# gondola.net
KiCad netlist of a schematic drawn in EAGLE
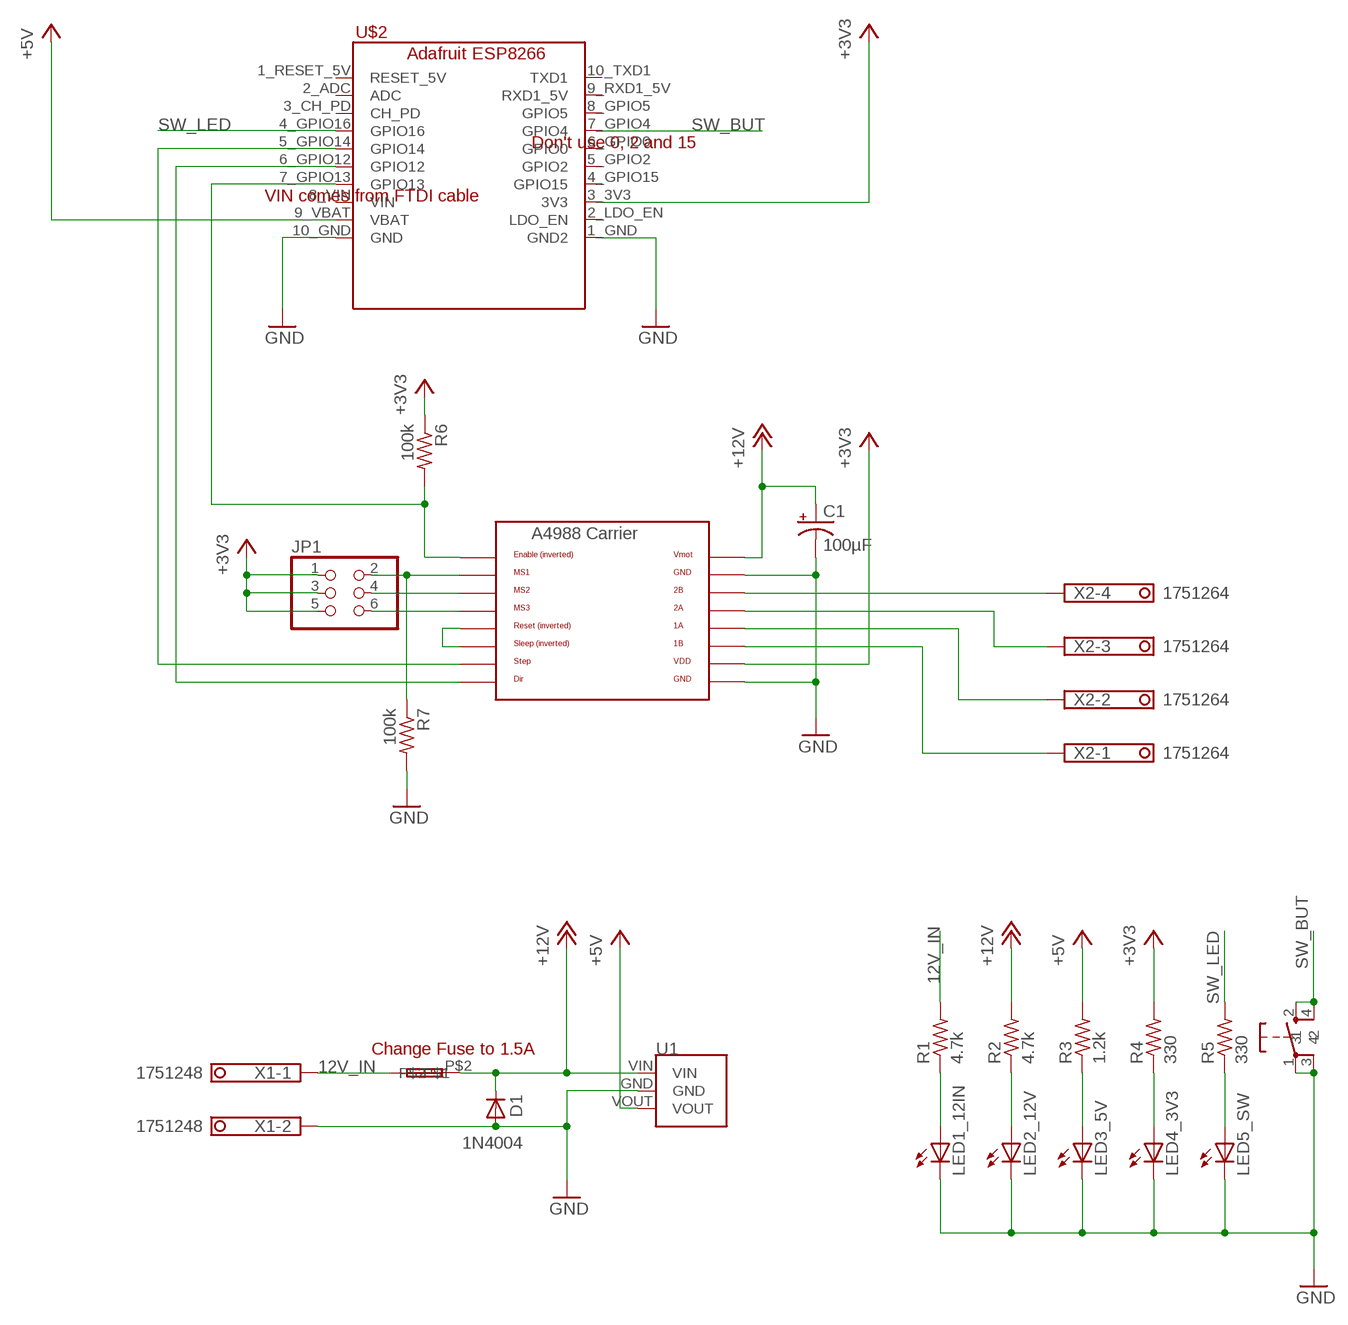
[diagram p0: schematic, sheet 1]

(export (version "E")
  (design (tool "Eeschema 10.0.6"))
  (components
    (comp (ref "C1")
      (value "100µF")
      (footprint "eagle-import:153CLV-0605")
      (libsource (lib "eagle-import") (part "CPOL-US153CLV-0605"))
    )
    (comp (ref "D1")
      (value "1N4004")
      (footprint "eagle-import:DO41-10")
      (libsource (lib "eagle-import") (part "1N4004"))
    )
    (comp (ref "F1")
      (value "MFR500")
      (footprint "eagle-import:MFR500")
      (libsource (lib "eagle-import") (part "MFR500"))
    )
    (comp (ref "JP1")
      (value "PINHD-2X3")
      (footprint "eagle-import:2X03")
      (libsource (lib "eagle-import") (part "PINHD-2X3"))
    )
    (comp (ref "LED1_12IN")
      (value "LEDCHIP-LED0805")
      (footprint "eagle-import:CHIP-LED0805")
      (libsource (lib "eagle-import") (part "LEDCHIP-LED0805"))
    )
    (comp (ref "LED2_12V")
      (value "LEDCHIP-LED0805")
      (footprint "eagle-import:CHIP-LED0805")
      (libsource (lib "eagle-import") (part "LEDCHIP-LED0805"))
    )
    (comp (ref "LED3_5V")
      (value "LEDCHIP-LED0805")
      (footprint "eagle-import:CHIP-LED0805")
      (libsource (lib "eagle-import") (part "LEDCHIP-LED0805"))
    )
    (comp (ref "LED4_3V3")
      (value "LEDCHIP-LED0805")
      (footprint "eagle-import:CHIP-LED0805")
      (libsource (lib "eagle-import") (part "LEDCHIP-LED0805"))
    )
    (comp (ref "LED5_SW")
      (value "LEDCHIP-LED0805")
      (footprint "eagle-import:CHIP-LED0805")
      (libsource (lib "eagle-import") (part "LEDCHIP-LED0805"))
    )
    (comp (ref "R1")
      (value "4.7k")
      (footprint "eagle-import:R0805")
      (libsource (lib "eagle-import") (part "R-US_R0805"))
    )
    (comp (ref "R2")
      (value "4.7k")
      (footprint "eagle-import:R0805")
      (libsource (lib "eagle-import") (part "R-US_R0805"))
    )
    (comp (ref "R3")
      (value "1.2k")
      (footprint "eagle-import:R0805")
      (libsource (lib "eagle-import") (part "R-US_R0805"))
    )
    (comp (ref "R4")
      (value "330")
      (footprint "eagle-import:R0805")
      (libsource (lib "eagle-import") (part "R-US_R0805"))
    )
    (comp (ref "R5")
      (value "330")
      (footprint "eagle-import:R0805")
      (libsource (lib "eagle-import") (part "R-US_R0805"))
    )
    (comp (ref "R6")
      (value "100k")
      (footprint "eagle-import:R0805")
      (libsource (lib "eagle-import") (part "R-US_R0805"))
    )
    (comp (ref "R7")
      (value "100k")
      (footprint "eagle-import:R0805")
      (libsource (lib "eagle-import") (part "R-US_R0805"))
    )
    (comp (ref "U$1")
      (value "A4988BREAKOUT")
      (footprint "eagle-import:A4988BREAKOUT")
      (libsource (lib "eagle-import") (part "A4988BREAKOUT"))
    )
    (comp (ref "U$2")
      (value "ADAFRUIT_ESP8266")
      (footprint "eagle-import:ADAFRUIT_ESP8266")
      (libsource (lib "eagle-import") (part "ADAFRUIT_ESP8266"))
    )
    (comp (ref "U$4")
      (value "FSMCTTR")
      (footprint "eagle-import:FSMCTTR")
      (libsource (lib "eagle-import") (part "FSMCTTR"))
    )
    (comp (ref "U1")
      (value "ROHM_BP5293-XX")
      (footprint "eagle-import:ROHM_BP5293-XX")
      (libsource (lib "eagle-import") (part "ROHM_BP5293-XX"))
    )
    (comp (ref "X1")
      (value "1751248")
      (footprint "eagle-import:1751248")
      (libsource (lib "eagle-import") (part "1751248"))
    )
    (comp (ref "X2")
      (value "1751264")
      (footprint "eagle-import:1751264")
      (libsource (lib "eagle-import") (part "1751264"))
    )
  )
  (nets
    (net (code "1") (name "+3V3") (class "Default")
      (node (ref "JP1") (pin "1") (pinfunction "1_1") (pintype "passive"))
      (node (ref "JP1") (pin "3") (pinfunction "3_3") (pintype "passive"))
      (node (ref "JP1") (pin "5") (pinfunction "5_5") (pintype "passive"))
      (node (ref "R4") (pin "2") (pinfunction "2_2") (pintype "passive"))
      (node (ref "R6") (pin "1") (pinfunction "1_1") (pintype "passive"))
      (node (ref "U$1") (pin "VDD") (pinfunction "VDD_VDD") (pintype "power_in"))
      (node (ref "U$2") (pin "3_3V3") (pinfunction "3V3_3_3V3") (pintype "bidirectional"))
    )
    (net (code "2") (name "+5V") (class "Default")
      (node (ref "R3") (pin "2") (pinfunction "2_2") (pintype "passive"))
      (node (ref "U$2") (pin "9_VBAT") (pinfunction "VBAT_9_VBAT") (pintype "bidirectional"))
      (node (ref "U1") (pin "VOUT") (pinfunction "VOUT_VOUT") (pintype "bidirectional"))
    )
    (net (code "3") (name "+12V") (class "Default")
      (node (ref "C1") (pin "+") (pinfunction "+_+") (pintype "passive"))
      (node (ref "D1") (pin "C") (pinfunction "C_C") (pintype "passive"))
      (node (ref "F1") (pin "P$2") (pinfunction "P$2_P$2") (pintype "bidirectional"))
      (node (ref "R2") (pin "2") (pinfunction "2_2") (pintype "passive"))
      (node (ref "U$1") (pin "VMOT") (pinfunction "VMOT_VMOT") (pintype "power_in"))
      (node (ref "U1") (pin "VIN") (pinfunction "VIN_VIN") (pintype "bidirectional"))
    )
    (net (code "4") (name "/12V_IN") (class "Default")
      (node (ref "F1") (pin "P$1") (pinfunction "P$1_P$1") (pintype "bidirectional"))
      (node (ref "R1") (pin "2") (pinfunction "2_2") (pintype "passive"))
      (node (ref "X1") (pin "1") (pinfunction "K_1") (pintype "passive"))
    )
    (net (code "5") (name "/SW_BUT") (class "Default")
      (node (ref "U$2") (pin "7_GPIO4") (pinfunction "GPIO4_7_GPIO4") (pintype "bidirectional"))
      (node (ref "U$4") (pin "2") (pinfunction "3_2") (pintype "bidirectional"))
      (node (ref "U$4") (pin "4") (pinfunction "4_4") (pintype "bidirectional"))
    )
    (net (code "6") (name "/SW_LED") (class "Default")
      (node (ref "R5") (pin "2") (pinfunction "2_2") (pintype "passive"))
      (node (ref "U$2") (pin "4_GPIO16") (pinfunction "GPIO16_4_GPIO16") (pintype "bidirectional"))
    )
    (net (code "7") (name "GND") (class "Default")
      (node (ref "C1") (pin "-") (pinfunction "-_-") (pintype "passive"))
      (node (ref "D1") (pin "A") (pinfunction "A_A") (pintype "passive"))
      (node (ref "LED1_12IN") (pin "C") (pinfunction "C_C") (pintype "passive"))
      (node (ref "LED2_12V") (pin "C") (pinfunction "C_C") (pintype "passive"))
      (node (ref "LED3_5V") (pin "C") (pinfunction "C_C") (pintype "passive"))
      (node (ref "LED4_3V3") (pin "C") (pinfunction "C_C") (pintype "passive"))
      (node (ref "LED5_SW") (pin "C") (pinfunction "C_C") (pintype "passive"))
      (node (ref "R7") (pin "2") (pinfunction "2_2") (pintype "passive"))
      (node (ref "U$1") (pin "GND") (pinfunction "GND_GND") (pintype "power_in"))
      (node (ref "U$1") (pin "GND@0") (pinfunction "GND_GND@0") (pintype "power_in"))
      (node (ref "U$2") (pin "10_GND") (pinfunction "GND_10_GND") (pintype "bidirectional"))
      (node (ref "U$2") (pin "1_GND") (pinfunction "GND2_1_GND") (pintype "bidirectional"))
      (node (ref "U$4") (pin "1") (pinfunction "1_1") (pintype "bidirectional"))
      (node (ref "U$4") (pin "3") (pinfunction "2_3") (pintype "bidirectional"))
      (node (ref "U1") (pin "GND") (pinfunction "GND_GND") (pintype "bidirectional"))
      (node (ref "X1") (pin "2") (pinfunction "K_2") (pintype "passive"))
    )
    (net (code "8") (name "Net-(JP1-Pad2)") (class "Default")
      (node (ref "JP1") (pin "2") (pinfunction "2_2") (pintype "passive"))
      (node (ref "R7") (pin "1") (pinfunction "1_1") (pintype "passive"))
      (node (ref "U$1") (pin "MS1") (pinfunction "MS1_MS1") (pintype "input"))
    )
    (net (code "9") (name "Net-(JP1-Pad4)") (class "Default")
      (node (ref "JP1") (pin "4") (pinfunction "4_4") (pintype "passive"))
      (node (ref "U$1") (pin "MS2") (pinfunction "MS2_MS2") (pintype "input"))
    )
    (net (code "10") (name "Net-(JP1-Pad6)") (class "Default")
      (node (ref "JP1") (pin "6") (pinfunction "6_6") (pintype "passive"))
      (node (ref "U$1") (pin "MS3") (pinfunction "MS3_MS3") (pintype "input"))
    )
    (net (code "11") (name "Net-(LED1_12IN-PadA)") (class "Default")
      (node (ref "LED1_12IN") (pin "A") (pinfunction "A_A") (pintype "passive"))
      (node (ref "R1") (pin "1") (pinfunction "1_1") (pintype "passive"))
    )
    (net (code "12") (name "Net-(LED2_12V-PadA)") (class "Default")
      (node (ref "LED2_12V") (pin "A") (pinfunction "A_A") (pintype "passive"))
      (node (ref "R2") (pin "1") (pinfunction "1_1") (pintype "passive"))
    )
    (net (code "13") (name "Net-(LED3_5V-PadA)") (class "Default")
      (node (ref "LED3_5V") (pin "A") (pinfunction "A_A") (pintype "passive"))
      (node (ref "R3") (pin "1") (pinfunction "1_1") (pintype "passive"))
    )
    (net (code "14") (name "Net-(LED4_3V3-PadA)") (class "Default")
      (node (ref "LED4_3V3") (pin "A") (pinfunction "A_A") (pintype "passive"))
      (node (ref "R4") (pin "1") (pinfunction "1_1") (pintype "passive"))
    )
    (net (code "15") (name "Net-(LED5_SW-PadA)") (class "Default")
      (node (ref "LED5_SW") (pin "A") (pinfunction "A_A") (pintype "passive"))
      (node (ref "R5") (pin "1") (pinfunction "1_1") (pintype "passive"))
    )
    (net (code "16") (name "Net-(U$1-SLEEP)") (class "Default")
      (node (ref "U$1") (pin "RST") (pinfunction "RST_RST") (pintype "input"))
      (node (ref "U$1") (pin "SLP") (pinfunction "SLEEP_SLP") (pintype "input"))
    )
    (net (code "17") (name "Net-(U$2-GPIO12)") (class "Default")
      (node (ref "U$1") (pin "DIR") (pinfunction "DIR_DIR") (pintype "input"))
      (node (ref "U$2") (pin "6_GPIO12") (pinfunction "GPIO12_6_GPIO12") (pintype "bidirectional"))
    )
    (net (code "18") (name "Net-(U$2-GPIO13)") (class "Default")
      (node (ref "R6") (pin "2") (pinfunction "2_2") (pintype "passive"))
      (node (ref "U$1") (pin "EN") (pinfunction "EN_EN") (pintype "input"))
      (node (ref "U$2") (pin "7_GPIO13") (pinfunction "GPIO13_7_GPIO13") (pintype "bidirectional"))
    )
    (net (code "19") (name "Net-(U$2-GPIO14)") (class "Default")
      (node (ref "U$1") (pin "STEP") (pinfunction "STEP_STEP") (pintype "input"))
      (node (ref "U$2") (pin "5_GPIO14") (pinfunction "GPIO14_5_GPIO14") (pintype "bidirectional"))
    )
    (net (code "20") (name "Net-(X2A-K)") (class "Default")
      (node (ref "U$1") (pin "1B") (pinfunction "1B_1B") (pintype "output"))
      (node (ref "X2") (pin "1") (pinfunction "K_1") (pintype "passive"))
    )
    (net (code "21") (name "Net-(X2B-K)") (class "Default")
      (node (ref "U$1") (pin "1A") (pinfunction "1A_1A") (pintype "output"))
      (node (ref "X2") (pin "2") (pinfunction "K_2") (pintype "passive"))
    )
    (net (code "22") (name "Net-(X2C-K)") (class "Default")
      (node (ref "U$1") (pin "2A") (pinfunction "2A_2A") (pintype "output"))
      (node (ref "X2") (pin "3") (pinfunction "K_3") (pintype "passive"))
    )
    (net (code "23") (name "Net-(X2D-K)") (class "Default")
      (node (ref "U$1") (pin "2B") (pinfunction "2B_2B") (pintype "output"))
      (node (ref "X2") (pin "4") (pinfunction "K_4") (pintype "passive"))
    )
    (net (code "24") (name "unconnected-(U$2-ADC-Pad2_ADC)") (class "Default")
      (node (ref "U$2") (pin "2_ADC") (pinfunction "ADC_2_ADC") (pintype "bidirectional"))
    )
    (net (code "25") (name "unconnected-(U$2-CH_PD-Pad3_CH_PD)") (class "Default")
      (node (ref "U$2") (pin "3_CH_PD") (pinfunction "CH_PD_3_CH_PD") (pintype "bidirectional"))
    )
    (net (code "26") (name "unconnected-(U$2-GPIO0-Pad6_GPIO0)") (class "Default")
      (node (ref "U$2") (pin "6_GPIO0") (pinfunction "GPIO0_6_GPIO0") (pintype "bidirectional"))
    )
    (net (code "27") (name "unconnected-(U$2-GPIO2-Pad5_GPIO2)") (class "Default")
      (node (ref "U$2") (pin "5_GPIO2") (pinfunction "GPIO2_5_GPIO2") (pintype "bidirectional"))
    )
    (net (code "28") (name "unconnected-(U$2-GPIO5-Pad8_GPIO5)") (class "Default")
      (node (ref "U$2") (pin "8_GPIO5") (pinfunction "GPIO5_8_GPIO5") (pintype "bidirectional"))
    )
    (net (code "29") (name "unconnected-(U$2-GPIO15-Pad4_GPIO15)") (class "Default")
      (node (ref "U$2") (pin "4_GPIO15") (pinfunction "GPIO15_4_GPIO15") (pintype "bidirectional"))
    )
    (net (code "30") (name "unconnected-(U$2-LDO_EN-Pad2_LDO_EN)") (class "Default")
      (node (ref "U$2") (pin "2_LDO_EN") (pinfunction "LDO_EN_2_LDO_EN") (pintype "bidirectional"))
    )
    (net (code "31") (name "unconnected-(U$2-RESET_5V-Pad1_RESET_5V)") (class "Default")
      (node (ref "U$2") (pin "1_RESET_5V") (pinfunction "RESET_5V_1_RESET_5V") (pintype "bidirectional"))
    )
    (net (code "32") (name "unconnected-(U$2-RXD1_5V-Pad9_RXD1_5V)") (class "Default")
      (node (ref "U$2") (pin "9_RXD1_5V") (pinfunction "RXD1_5V_9_RXD1_5V") (pintype "bidirectional"))
    )
    (net (code "33") (name "unconnected-(U$2-TXD1-Pad10_TXD1)") (class "Default")
      (node (ref "U$2") (pin "10_TXD1") (pinfunction "TXD1_10_TXD1") (pintype "bidirectional"))
    )
    (net (code "34") (name "unconnected-(U$2-VIN-Pad8_VIN)") (class "Default")
      (node (ref "U$2") (pin "8_VIN") (pinfunction "VIN_8_VIN") (pintype "bidirectional"))
    )
  )
)
